# labwiz-module_pH-0_2.net
KiCad netlist of a schematic drawn in EAGLE
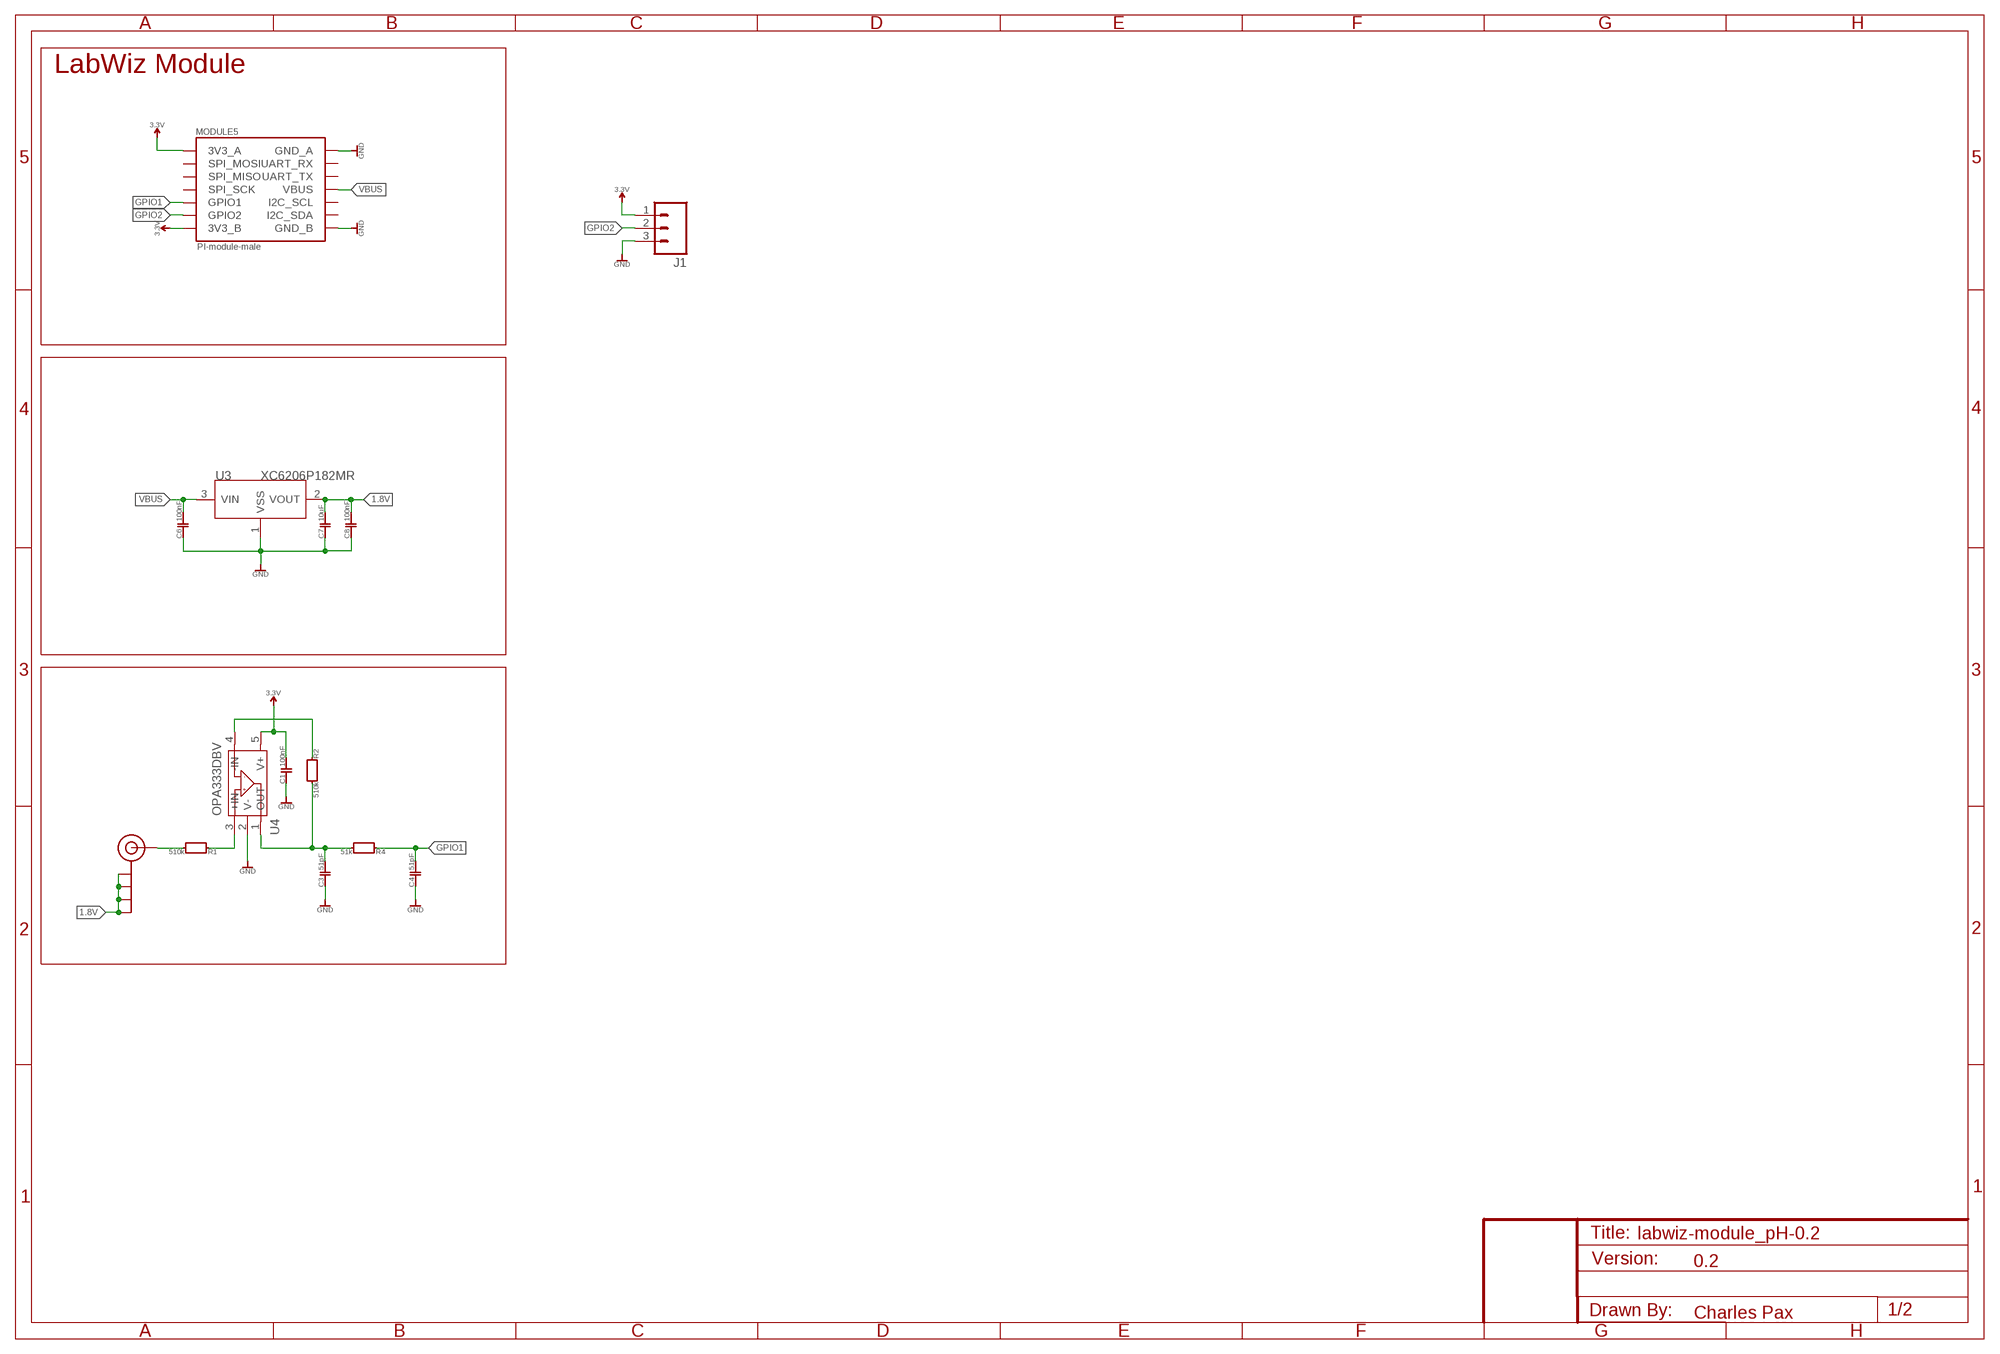
[diagram p0: schematic, sheet 1]

(export (version "E")
  (design (tool "Eeschema 10.0.6"))
  (components
    (comp (ref "C1")
      (value "100nF")
      (footprint "eagle-import:0603")
      (libsource (lib "eagle-import") (part "CAPACITOR_FIXED_0603_100NF"))
    )
    (comp (ref "C3")
      (value "51pF")
      (footprint "eagle-import:0603")
      (libsource (lib "eagle-import") (part "CAPACITOR_FIXED_0603"))
    )
    (comp (ref "C4")
      (value "51pF")
      (footprint "eagle-import:0603")
      (libsource (lib "eagle-import") (part "CAPACITOR_FIXED_0603"))
    )
    (comp (ref "C6")
      (value "100nF")
      (footprint "eagle-import:0603")
      (libsource (lib "eagle-import") (part "CAPACITOR_FIXED_0603_100NF"))
    )
    (comp (ref "C7")
      (value "10uF")
      (footprint "eagle-import:0603")
      (libsource (lib "eagle-import") (part "CAPACITOR_FIXED_0603_10UF"))
    )
    (comp (ref "C8")
      (value "100nF")
      (footprint "eagle-import:0603")
      (libsource (lib "eagle-import") (part "CAPACITOR_FIXED_0603_100NF"))
    )
    (comp (ref "J$1")
      (value "SMA_EDGE")
      (footprint "eagle-import:SMA-EDGE")
      (libsource (lib "eagle-import") (part "SMA_EDGE"))
    )
    (comp (ref "J1")
      (value "M03LOCK_LONGPADS")
      (footprint "eagle-import:1X03_LOCK_LONGPADS")
      (libsource (lib "eagle-import") (part "M03LOCK_LONGPADS"))
    )
    (comp (ref "MODULE5")
      (value "PI-module-male")
      (footprint "eagle-import:M07X2_2MM_EDGE")
      (fields (field (name "MF") "Pax Instruments") (field (name "MPN") "PIxxxx"))
      (libsource (lib "eagle-import") (part "PAX_MODULE_EDGE_MALE_MODULE"))
    )
    (comp (ref "R1")
      (value "510k")
      (footprint "eagle-import:0603")
      (libsource (lib "eagle-import") (part "RESISTOR_FIXED_0603"))
    )
    (comp (ref "R2")
      (value "510k")
      (footprint "eagle-import:0603")
      (libsource (lib "eagle-import") (part "RESISTOR_FIXED_0603"))
    )
    (comp (ref "R4")
      (value "51k")
      (footprint "eagle-import:0603")
      (libsource (lib "eagle-import") (part "RESISTOR_FIXED_0603"))
    )
    (comp (ref "U3")
      (value "XC6206P182MR")
      (footprint "eagle-import:SOT23")
      (libsource (lib "eagle-import") (part "XC6206MR"))
    )
    (comp (ref "U4")
      (value "OPA333DBV")
      (footprint "eagle-import:SOT23-5")
      (libsource (lib "eagle-import") (part "OPA333DBV"))
    )
  )
  (nets
    (net (code "1") (name "1.8V") (class "Default")
      (node (ref "C7") (pin "2") (pinfunction "2_2") (pintype "passive"))
      (node (ref "C8") (pin "2") (pinfunction "2_2") (pintype "passive"))
      (node (ref "J$1") (pin "GND@0") (pinfunction "GND_GND@0") (pintype "bidirectional"))
      (node (ref "J$1") (pin "GND@1") (pinfunction "GND_GND@1") (pintype "bidirectional"))
      (node (ref "J$1") (pin "GND@2") (pinfunction "GND_GND@2") (pintype "bidirectional"))
      (node (ref "J$1") (pin "GND@3") (pinfunction "GND_GND@3") (pintype "bidirectional"))
      (node (ref "U3") (pin "2") (pinfunction "VOUT_2") (pintype "output"))
    )
    (net (code "2") (name "3.3V") (class "Default")
      (node (ref "C1") (pin "2") (pinfunction "2_2") (pintype "passive"))
      (node (ref "J1") (pin "1") (pinfunction "1_1") (pintype "passive"))
      (node (ref "MODULE5") (pin "P$1") (pinfunction "3V3_B_P$1") (pintype "bidirectional"))
      (node (ref "MODULE5") (pin "P$13") (pinfunction "3V3_A_P$13") (pintype "power_in"))
      (node (ref "U4") (pin "5") (pinfunction "V+_5") (pintype "bidirectional"))
    )
    (net (code "3") (name "GND") (class "Default")
      (node (ref "C1") (pin "1") (pinfunction "1_1") (pintype "passive"))
      (node (ref "C3") (pin "1") (pinfunction "1_1") (pintype "passive"))
      (node (ref "C4") (pin "1") (pinfunction "1_1") (pintype "passive"))
      (node (ref "C6") (pin "1") (pinfunction "1_1") (pintype "passive"))
      (node (ref "C7") (pin "1") (pinfunction "1_1") (pintype "passive"))
      (node (ref "C8") (pin "1") (pinfunction "1_1") (pintype "passive"))
      (node (ref "J1") (pin "3") (pinfunction "3_3") (pintype "passive"))
      (node (ref "MODULE5") (pin "P$14") (pinfunction "GND_A_P$14") (pintype "power_in"))
      (node (ref "MODULE5") (pin "P$2") (pinfunction "GND_B_P$2") (pintype "bidirectional"))
      (node (ref "U3") (pin "1") (pinfunction "VSS_1") (pintype "power_in"))
      (node (ref "U4") (pin "2") (pinfunction "V-_2") (pintype "bidirectional"))
    )
    (net (code "4") (name "GPIO1") (class "Default")
      (node (ref "C4") (pin "2") (pinfunction "2_2") (pintype "passive"))
      (node (ref "MODULE5") (pin "P$5") (pinfunction "GPIO1_P$5") (pintype "bidirectional"))
      (node (ref "R4") (pin "2") (pinfunction "2_2") (pintype "passive"))
    )
    (net (code "5") (name "GPIO2") (class "Default")
      (node (ref "J1") (pin "2") (pinfunction "2_2") (pintype "passive"))
      (node (ref "MODULE5") (pin "P$3") (pinfunction "GPIO2_P$3") (pintype "bidirectional"))
    )
    (net (code "6") (name "Net-(J$1-SIGNAL)") (class "Default")
      (node (ref "J$1") (pin "SIG") (pinfunction "SIGNAL_SIG") (pintype "bidirectional"))
      (node (ref "R1") (pin "1") (pinfunction "1_1") (pintype "passive"))
    )
    (net (code "7") (name "Net-(U4-+IN)") (class "Default")
      (node (ref "R1") (pin "2") (pinfunction "2_2") (pintype "passive"))
      (node (ref "U4") (pin "3") (pinfunction "+IN_3") (pintype "bidirectional"))
    )
    (net (code "8") (name "Net-(U4--IN)") (class "Default")
      (node (ref "R2") (pin "2") (pinfunction "2_2") (pintype "passive"))
      (node (ref "U4") (pin "4") (pinfunction "-IN_4") (pintype "bidirectional"))
    )
    (net (code "9") (name "Net-(U4-OUT)") (class "Default")
      (node (ref "C3") (pin "2") (pinfunction "2_2") (pintype "passive"))
      (node (ref "R2") (pin "1") (pinfunction "1_1") (pintype "passive"))
      (node (ref "R4") (pin "1") (pinfunction "1_1") (pintype "passive"))
      (node (ref "U4") (pin "1") (pinfunction "OUT_1") (pintype "bidirectional"))
    )
    (net (code "10") (name "VBUS") (class "Default")
      (node (ref "C6") (pin "2") (pinfunction "2_2") (pintype "passive"))
      (node (ref "MODULE5") (pin "P$8") (pinfunction "VBUS_P$8") (pintype "bidirectional"))
      (node (ref "U3") (pin "3") (pinfunction "VIN_3") (pintype "input"))
    )
    (net (code "11") (name "unconnected-(MODULE5-I2C_SCL-PadP$6)") (class "Default")
      (node (ref "MODULE5") (pin "P$6") (pinfunction "I2C_SCL_P$6") (pintype "bidirectional"))
    )
    (net (code "12") (name "unconnected-(MODULE5-I2C_SDA-PadP$4)") (class "Default")
      (node (ref "MODULE5") (pin "P$4") (pinfunction "I2C_SDA_P$4") (pintype "bidirectional"))
    )
    (net (code "13") (name "unconnected-(MODULE5-SPI_MISO-PadP$9)") (class "Default")
      (node (ref "MODULE5") (pin "P$9") (pinfunction "SPI_MISO_P$9") (pintype "bidirectional"))
    )
    (net (code "14") (name "unconnected-(MODULE5-SPI_MOSI-PadP$11)") (class "Default")
      (node (ref "MODULE5") (pin "P$11") (pinfunction "SPI_MOSI_P$11") (pintype "bidirectional"))
    )
    (net (code "15") (name "unconnected-(MODULE5-SPI_SCK-PadP$7)") (class "Default")
      (node (ref "MODULE5") (pin "P$7") (pinfunction "SPI_SCK_P$7") (pintype "bidirectional"))
    )
    (net (code "16") (name "unconnected-(MODULE5-UART_RX-PadP$12)") (class "Default")
      (node (ref "MODULE5") (pin "P$12") (pinfunction "UART_RX_P$12") (pintype "bidirectional"))
    )
    (net (code "17") (name "unconnected-(MODULE5-UART_TX-PadP$10)") (class "Default")
      (node (ref "MODULE5") (pin "P$10") (pinfunction "UART_TX_P$10") (pintype "bidirectional"))
    )
  )
)
